# 3P4W_v1p2.net
KiCad netlist of a schematic drawn in EAGLE
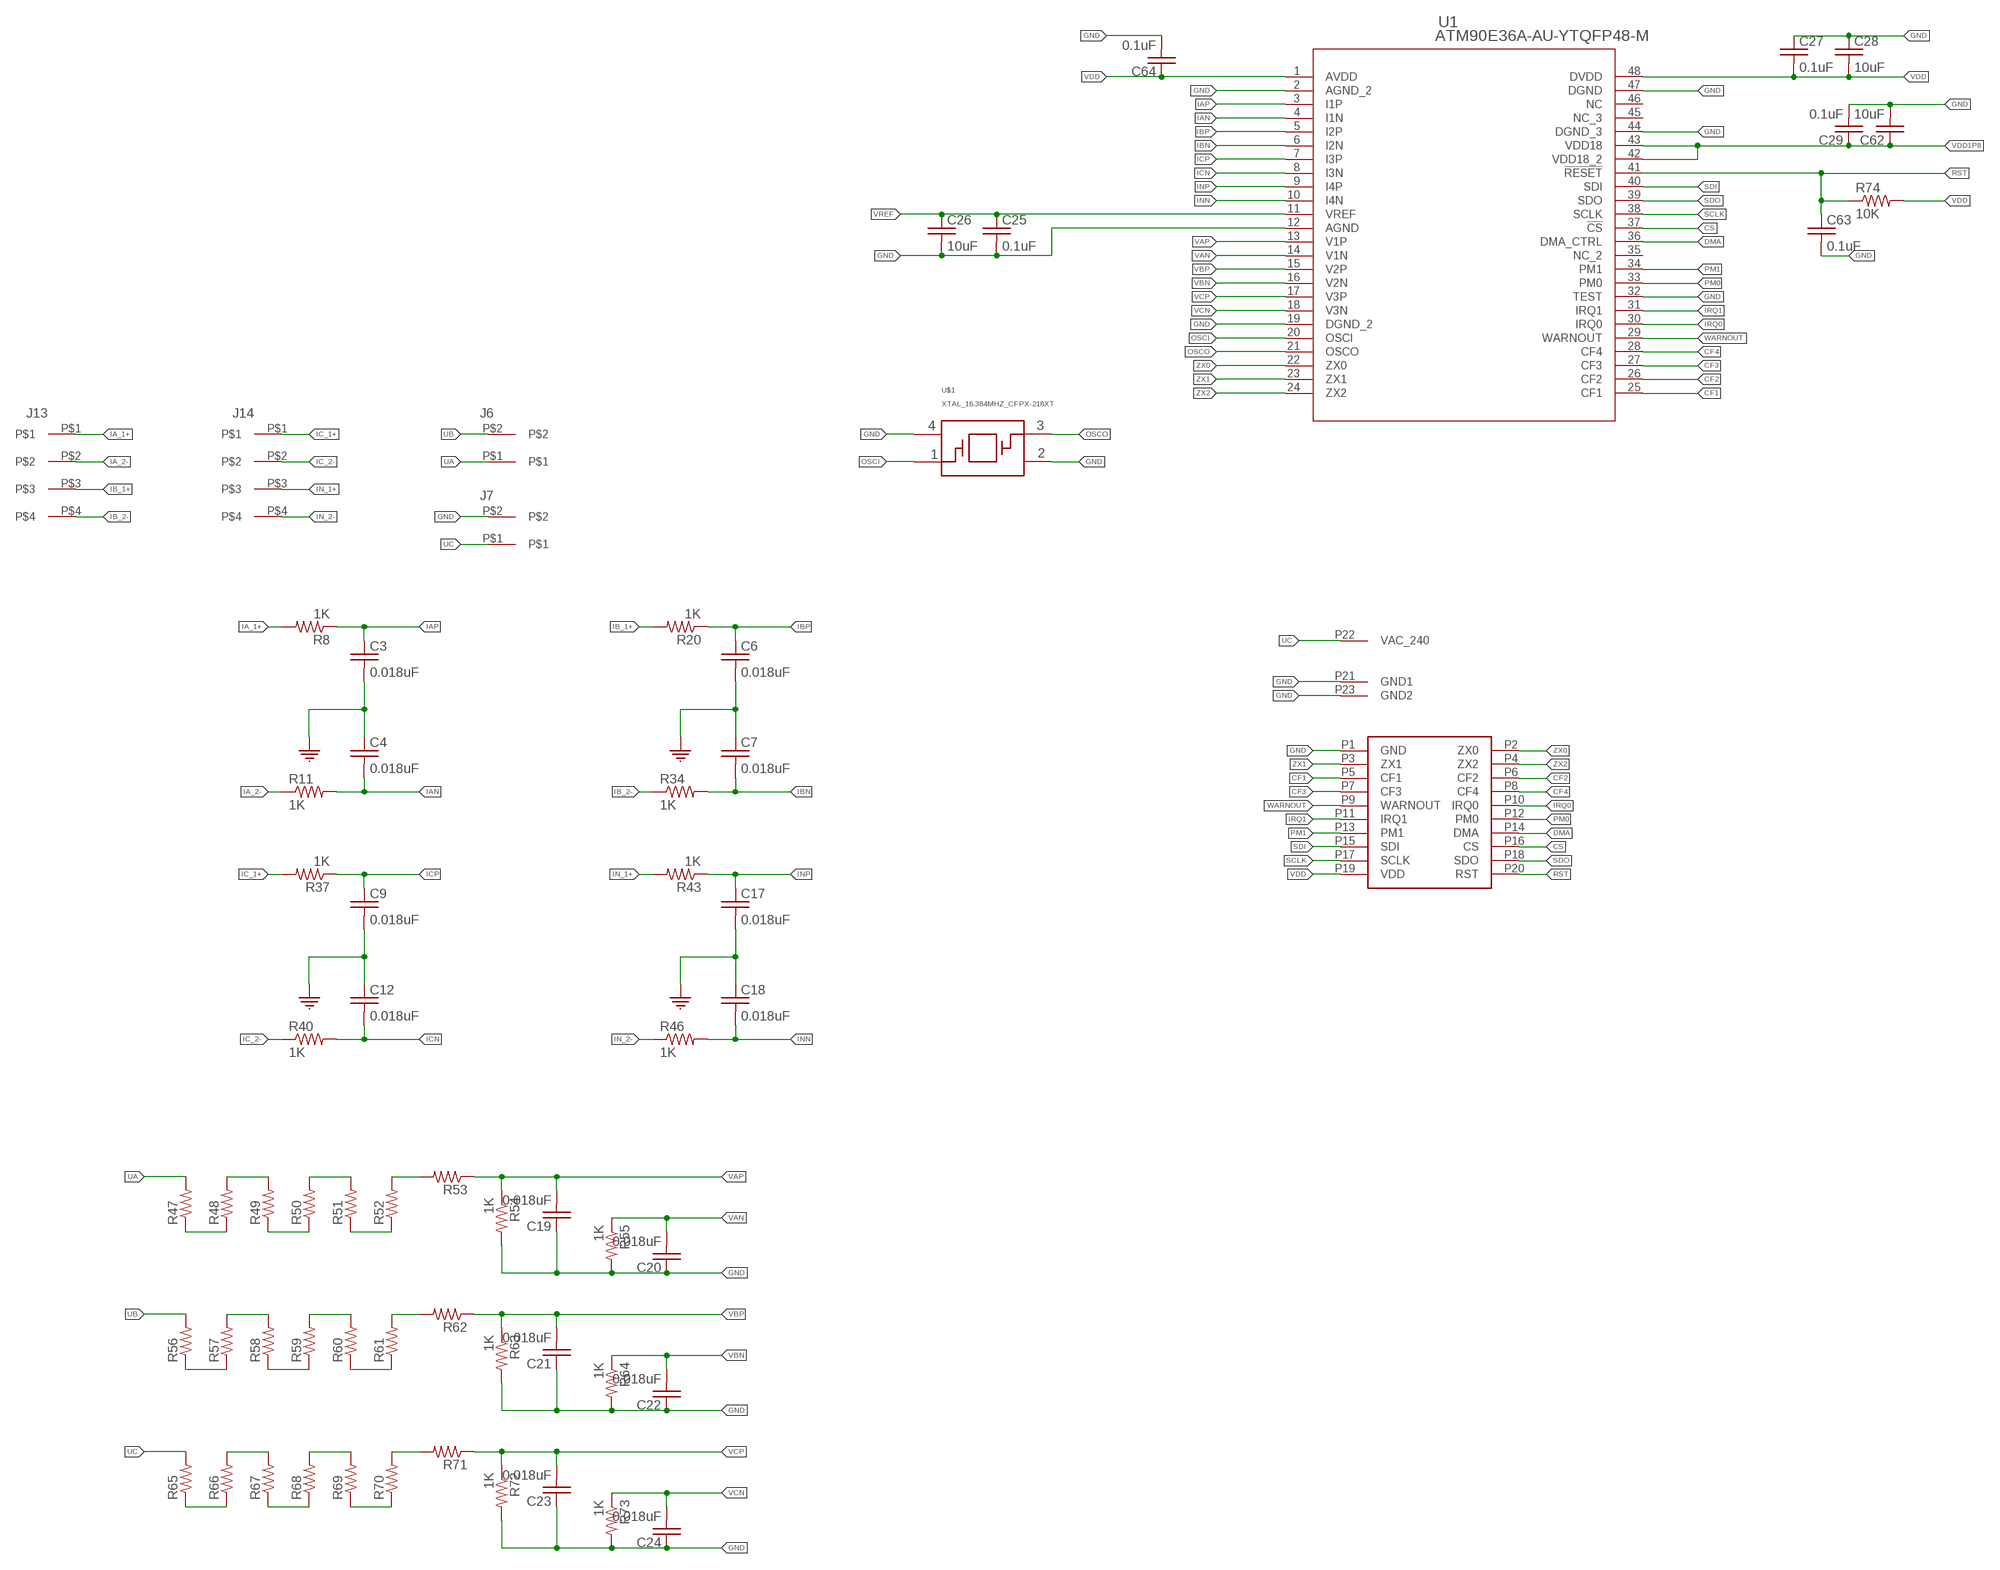
[diagram p0: schematic, sheet 1]

(export (version "E")
  (design (tool "Eeschema 10.0.6"))
  (components
    (comp (ref "C3")
      (value "0.018uF")
      (footprint "eagle-import:0402")
      (libsource (lib "eagle-import") (part "C_0402"))
    )
    (comp (ref "C4")
      (value "0.018uF")
      (footprint "eagle-import:0402")
      (libsource (lib "eagle-import") (part "C_0402"))
    )
    (comp (ref "C6")
      (value "0.018uF")
      (footprint "eagle-import:0402")
      (libsource (lib "eagle-import") (part "C_0402"))
    )
    (comp (ref "C7")
      (value "0.018uF")
      (footprint "eagle-import:0402")
      (libsource (lib "eagle-import") (part "C_0402"))
    )
    (comp (ref "C9")
      (value "0.018uF")
      (footprint "eagle-import:0402")
      (libsource (lib "eagle-import") (part "C_0402"))
    )
    (comp (ref "C12")
      (value "0.018uF")
      (footprint "eagle-import:0402")
      (libsource (lib "eagle-import") (part "C_0402"))
    )
    (comp (ref "C17")
      (value "0.018uF")
      (footprint "eagle-import:0402")
      (libsource (lib "eagle-import") (part "C_0402"))
    )
    (comp (ref "C18")
      (value "0.018uF")
      (footprint "eagle-import:0402")
      (libsource (lib "eagle-import") (part "C_0402"))
    )
    (comp (ref "C19")
      (value "0.018uF")
      (footprint "eagle-import:0402")
      (libsource (lib "eagle-import") (part "C_0402"))
    )
    (comp (ref "C20")
      (value "0.018uF")
      (footprint "eagle-import:0402")
      (libsource (lib "eagle-import") (part "C_0402"))
    )
    (comp (ref "C21")
      (value "0.018uF")
      (footprint "eagle-import:0402")
      (libsource (lib "eagle-import") (part "C_0402"))
    )
    (comp (ref "C22")
      (value "0.018uF")
      (footprint "eagle-import:0402")
      (libsource (lib "eagle-import") (part "C_0402"))
    )
    (comp (ref "C23")
      (value "0.018uF")
      (footprint "eagle-import:0402")
      (libsource (lib "eagle-import") (part "C_0402"))
    )
    (comp (ref "C24")
      (value "0.018uF")
      (footprint "eagle-import:0402")
      (libsource (lib "eagle-import") (part "C_0402"))
    )
    (comp (ref "C25")
      (value "0.1uF")
      (footprint "eagle-import:0402")
      (libsource (lib "eagle-import") (part "C_0402"))
    )
    (comp (ref "C26")
      (value "10uF")
      (footprint "eagle-import:0402")
      (libsource (lib "eagle-import") (part "C_0402"))
    )
    (comp (ref "C27")
      (value "0.1uF")
      (footprint "eagle-import:0402")
      (libsource (lib "eagle-import") (part "C_0402"))
    )
    (comp (ref "C28")
      (value "10uF")
      (footprint "eagle-import:0402")
      (libsource (lib "eagle-import") (part "C_0402"))
    )
    (comp (ref "C29")
      (value "0.1uF")
      (footprint "eagle-import:0402")
      (libsource (lib "eagle-import") (part "C_0402"))
    )
    (comp (ref "C62")
      (value "10uF")
      (footprint "eagle-import:0402")
      (libsource (lib "eagle-import") (part "C_0402"))
    )
    (comp (ref "C63")
      (value "0.1uF")
      (footprint "eagle-import:0402")
      (libsource (lib "eagle-import") (part "C_0402"))
    )
    (comp (ref "C64")
      (value "0.1uF")
      (footprint "eagle-import:0402")
      (libsource (lib "eagle-import") (part "C_0402"))
    )
    (comp (ref "J6")
      (value "3.81MM_1_X_2_RT_ANGLE_PLUG_HEADER")
      (footprint "eagle-import:2_3.81MM_PITCH")
      (libsource (lib "eagle-import") (part "3.81MM_1_X_2_RT_ANGLE_PLUG_HEADER"))
    )
    (comp (ref "J7")
      (value "3.81MM_1_X_2_RT_ANGLE_PLUG_HEADER")
      (footprint "eagle-import:2_3.81MM_PITCH")
      (libsource (lib "eagle-import") (part "3.81MM_1_X_2_RT_ANGLE_PLUG_HEADER"))
    )
    (comp (ref "J13")
      (value "3.81MM_1_X_4_RT_ANGLE_PLUG_HEADER")
      (footprint "eagle-import:1X4_3.81MM_PITCH")
      (libsource (lib "eagle-import") (part "3.81MM_1_X_4_RT_ANGLE_PLUG_HEADER"))
    )
    (comp (ref "J14")
      (value "3.81MM_1_X_4_RT_ANGLE_PLUG_HEADER")
      (footprint "eagle-import:1X4_3.81MM_PITCH")
      (libsource (lib "eagle-import") (part "3.81MM_1_X_4_RT_ANGLE_PLUG_HEADER"))
    )
    (comp (ref "R8")
      (value "1K")
      (footprint "eagle-import:0402")
      (libsource (lib "eagle-import") (part "R_0402"))
    )
    (comp (ref "R11")
      (value "1K")
      (footprint "eagle-import:0402")
      (libsource (lib "eagle-import") (part "R_0402"))
    )
    (comp (ref "R20")
      (value "1K")
      (footprint "eagle-import:0402")
      (libsource (lib "eagle-import") (part "R_0402"))
    )
    (comp (ref "R34")
      (value "1K")
      (footprint "eagle-import:0402")
      (libsource (lib "eagle-import") (part "R_0402"))
    )
    (comp (ref "R37")
      (value "1K")
      (footprint "eagle-import:0402")
      (libsource (lib "eagle-import") (part "R_0402"))
    )
    (comp (ref "R40")
      (value "1K")
      (footprint "eagle-import:0402")
      (libsource (lib "eagle-import") (part "R_0402"))
    )
    (comp (ref "R43")
      (value "1K")
      (footprint "eagle-import:0402")
      (libsource (lib "eagle-import") (part "R_0402"))
    )
    (comp (ref "R46")
      (value "1K")
      (footprint "eagle-import:0402")
      (libsource (lib "eagle-import") (part "R_0402"))
    )
    (comp (ref "R47")
      (value "R_0402")
      (footprint "eagle-import:0402")
      (libsource (lib "eagle-import") (part "R_0402"))
    )
    (comp (ref "R48")
      (value "R_0402")
      (footprint "eagle-import:0402")
      (libsource (lib "eagle-import") (part "R_0402"))
    )
    (comp (ref "R49")
      (value "R_0402")
      (footprint "eagle-import:0402")
      (libsource (lib "eagle-import") (part "R_0402"))
    )
    (comp (ref "R50")
      (value "R_0402")
      (footprint "eagle-import:0402")
      (libsource (lib "eagle-import") (part "R_0402"))
    )
    (comp (ref "R51")
      (value "R_0402")
      (footprint "eagle-import:0402")
      (libsource (lib "eagle-import") (part "R_0402"))
    )
    (comp (ref "R52")
      (value "R_0402")
      (footprint "eagle-import:0402")
      (libsource (lib "eagle-import") (part "R_0402"))
    )
    (comp (ref "R53")
      (value "R_0402")
      (footprint "eagle-import:0402")
      (libsource (lib "eagle-import") (part "R_0402"))
    )
    (comp (ref "R54")
      (value "1K")
      (footprint "eagle-import:0402")
      (libsource (lib "eagle-import") (part "R_0402"))
    )
    (comp (ref "R55")
      (value "1K")
      (footprint "eagle-import:0402")
      (libsource (lib "eagle-import") (part "R_0402"))
    )
    (comp (ref "R56")
      (value "R_0402")
      (footprint "eagle-import:0402")
      (libsource (lib "eagle-import") (part "R_0402"))
    )
    (comp (ref "R57")
      (value "R_0402")
      (footprint "eagle-import:0402")
      (libsource (lib "eagle-import") (part "R_0402"))
    )
    (comp (ref "R58")
      (value "R_0402")
      (footprint "eagle-import:0402")
      (libsource (lib "eagle-import") (part "R_0402"))
    )
    (comp (ref "R59")
      (value "R_0402")
      (footprint "eagle-import:0402")
      (libsource (lib "eagle-import") (part "R_0402"))
    )
    (comp (ref "R60")
      (value "R_0402")
      (footprint "eagle-import:0402")
      (libsource (lib "eagle-import") (part "R_0402"))
    )
    (comp (ref "R61")
      (value "R_0402")
      (footprint "eagle-import:0402")
      (libsource (lib "eagle-import") (part "R_0402"))
    )
    (comp (ref "R62")
      (value "R_0402")
      (footprint "eagle-import:0402")
      (libsource (lib "eagle-import") (part "R_0402"))
    )
    (comp (ref "R63")
      (value "1K")
      (footprint "eagle-import:0402")
      (libsource (lib "eagle-import") (part "R_0402"))
    )
    (comp (ref "R64")
      (value "1K")
      (footprint "eagle-import:0402")
      (libsource (lib "eagle-import") (part "R_0402"))
    )
    (comp (ref "R65")
      (value "R_0402")
      (footprint "eagle-import:0402")
      (libsource (lib "eagle-import") (part "R_0402"))
    )
    (comp (ref "R66")
      (value "R_0402")
      (footprint "eagle-import:0402")
      (libsource (lib "eagle-import") (part "R_0402"))
    )
    (comp (ref "R67")
      (value "R_0402")
      (footprint "eagle-import:0402")
      (libsource (lib "eagle-import") (part "R_0402"))
    )
    (comp (ref "R68")
      (value "R_0402")
      (footprint "eagle-import:0402")
      (libsource (lib "eagle-import") (part "R_0402"))
    )
    (comp (ref "R69")
      (value "R_0402")
      (footprint "eagle-import:0402")
      (libsource (lib "eagle-import") (part "R_0402"))
    )
    (comp (ref "R70")
      (value "R_0402")
      (footprint "eagle-import:0402")
      (libsource (lib "eagle-import") (part "R_0402"))
    )
    (comp (ref "R71")
      (value "R_0402")
      (footprint "eagle-import:0402")
      (libsource (lib "eagle-import") (part "R_0402"))
    )
    (comp (ref "R72")
      (value "1K")
      (footprint "eagle-import:0402")
      (libsource (lib "eagle-import") (part "R_0402"))
    )
    (comp (ref "R73")
      (value "1K")
      (footprint "eagle-import:0402")
      (libsource (lib "eagle-import") (part "R_0402"))
    )
    (comp (ref "R74")
      (value "10K")
      (footprint "eagle-import:0402")
      (libsource (lib "eagle-import") (part "R_0402"))
    )
    (comp (ref "U$1")
      (value "XTAL_16.384MHZ_CFPX-218XT")
      (footprint "eagle-import:XTAL_2.5X2.0")
      (libsource (lib "eagle-import") (part "XTAL_16.384MHZ_CFPX-218XT"))
    )
    (comp (ref "U$2")
      (value "METER_BASE")
      (footprint "eagle-import:METER_BASE")
      (libsource (lib "eagle-import") (part "METER_BASE"))
    )
    (comp (ref "U1")
      (value "ATM90E36A-AU-YTQFP48-M")
      (footprint "eagle-import:TQFP48-M")
      (fields (field (name "MANUFACTURER_PART_NUMBER") "ATM90E36AAUY"))
      (libsource (lib "eagle-import") (part "ATM90E36A-AU-YTQFP48-M"))
    )
  )
  (nets
    (net (code "1") (name "CF1") (class "Default")
      (node (ref "U$2") (pin "P5") (pinfunction "CF1_P5") (pintype "bidirectional"))
      (node (ref "U1") (pin "25") (pinfunction "CF1_25") (pintype "output"))
    )
    (net (code "2") (name "CF2") (class "Default")
      (node (ref "U$2") (pin "P6") (pinfunction "CF2_P6") (pintype "bidirectional"))
      (node (ref "U1") (pin "26") (pinfunction "CF2_26") (pintype "output"))
    )
    (net (code "3") (name "CF3") (class "Default")
      (node (ref "U$2") (pin "P7") (pinfunction "CF3_P7") (pintype "bidirectional"))
      (node (ref "U1") (pin "27") (pinfunction "CF3_27") (pintype "output"))
    )
    (net (code "4") (name "CF4") (class "Default")
      (node (ref "U$2") (pin "P8") (pinfunction "CF4_P8") (pintype "bidirectional"))
      (node (ref "U1") (pin "28") (pinfunction "CF4_28") (pintype "output"))
    )
    (net (code "5") (name "CS") (class "Default")
      (node (ref "U$2") (pin "P16") (pinfunction "CS_P16") (pintype "bidirectional"))
      (node (ref "U1") (pin "37") (pinfunction "~{CS}_37") (pintype "bidirectional"))
    )
    (net (code "6") (name "DMA") (class "Default")
      (node (ref "U$2") (pin "P14") (pinfunction "DMA_P14") (pintype "bidirectional"))
      (node (ref "U1") (pin "36") (pinfunction "DMA_CTRL_36") (pintype "input"))
    )
    (net (code "7") (name "GND") (class "Default")
      (node (ref "C12") (pin "P$1") (pinfunction "1_P$1") (pintype "passive"))
      (node (ref "C17") (pin "P$2") (pinfunction "2_P$2") (pintype "passive"))
      (node (ref "C18") (pin "P$1") (pinfunction "1_P$1") (pintype "passive"))
      (node (ref "C19") (pin "P$1") (pinfunction "1_P$1") (pintype "passive"))
      (node (ref "C20") (pin "P$1") (pinfunction "1_P$1") (pintype "passive"))
      (node (ref "C21") (pin "P$1") (pinfunction "1_P$1") (pintype "passive"))
      (node (ref "C22") (pin "P$1") (pinfunction "1_P$1") (pintype "passive"))
      (node (ref "C23") (pin "P$1") (pinfunction "1_P$1") (pintype "passive"))
      (node (ref "C24") (pin "P$1") (pinfunction "1_P$1") (pintype "passive"))
      (node (ref "C25") (pin "P$2") (pinfunction "2_P$2") (pintype "passive"))
      (node (ref "C26") (pin "P$2") (pinfunction "2_P$2") (pintype "passive"))
      (node (ref "C27") (pin "P$1") (pinfunction "1_P$1") (pintype "passive"))
      (node (ref "C28") (pin "P$1") (pinfunction "1_P$1") (pintype "passive"))
      (node (ref "C29") (pin "P$2") (pinfunction "2_P$2") (pintype "passive"))
      (node (ref "C3") (pin "P$2") (pinfunction "2_P$2") (pintype "passive"))
      (node (ref "C4") (pin "P$1") (pinfunction "1_P$1") (pintype "passive"))
      (node (ref "C6") (pin "P$2") (pinfunction "2_P$2") (pintype "passive"))
      (node (ref "C62") (pin "P$2") (pinfunction "2_P$2") (pintype "passive"))
      (node (ref "C63") (pin "P$2") (pinfunction "2_P$2") (pintype "passive"))
      (node (ref "C64") (pin "P$2") (pinfunction "2_P$2") (pintype "passive"))
      (node (ref "C7") (pin "P$1") (pinfunction "1_P$1") (pintype "passive"))
      (node (ref "C9") (pin "P$2") (pinfunction "2_P$2") (pintype "passive"))
      (node (ref "J7") (pin "P$2") (pinfunction "P$2_P$2") (pintype "bidirectional"))
      (node (ref "R54") (pin "P$2") (pinfunction "2_P$2") (pintype "passive"))
      (node (ref "R55") (pin "P$2") (pinfunction "2_P$2") (pintype "passive"))
      (node (ref "R63") (pin "P$2") (pinfunction "2_P$2") (pintype "passive"))
      (node (ref "R64") (pin "P$2") (pinfunction "2_P$2") (pintype "passive"))
      (node (ref "R72") (pin "P$2") (pinfunction "2_P$2") (pintype "passive"))
      (node (ref "R73") (pin "P$2") (pinfunction "2_P$2") (pintype "passive"))
      (node (ref "U$1") (pin "2") (pinfunction "2_2") (pintype "bidirectional"))
      (node (ref "U$1") (pin "4") (pinfunction "4_4") (pintype "bidirectional"))
      (node (ref "U$2") (pin "P1") (pinfunction "GND_P1") (pintype "bidirectional"))
      (node (ref "U$2") (pin "P21") (pinfunction "GND1_P21") (pintype "bidirectional"))
      (node (ref "U$2") (pin "P23") (pinfunction "GND2_P23") (pintype "bidirectional"))
      (node (ref "U1") (pin "12") (pinfunction "AGND_12") (pintype "power_in"))
      (node (ref "U1") (pin "19") (pinfunction "DGND_2_19") (pintype "power_in"))
      (node (ref "U1") (pin "2") (pinfunction "AGND_2_2") (pintype "power_in"))
      (node (ref "U1") (pin "32") (pinfunction "TEST_32") (pintype "input"))
      (node (ref "U1") (pin "44") (pinfunction "DGND_3_44") (pintype "power_in"))
      (node (ref "U1") (pin "47") (pinfunction "DGND_47") (pintype "power_in"))
    )
    (net (code "8") (name "IAN") (class "Default")
      (node (ref "C4") (pin "P$2") (pinfunction "2_P$2") (pintype "passive"))
      (node (ref "R11") (pin "P$2") (pinfunction "2_P$2") (pintype "passive"))
      (node (ref "U1") (pin "4") (pinfunction "I1N_4") (pintype "input"))
    )
    (net (code "9") (name "IAP") (class "Default")
      (node (ref "C3") (pin "P$1") (pinfunction "1_P$1") (pintype "passive"))
      (node (ref "R8") (pin "P$1") (pinfunction "1_P$1") (pintype "passive"))
      (node (ref "U1") (pin "3") (pinfunction "I1P_3") (pintype "input"))
    )
    (net (code "10") (name "IA_1+") (class "Default")
      (node (ref "J13") (pin "P$1") (pinfunction "P$1_P$1") (pintype "bidirectional"))
      (node (ref "R8") (pin "P$2") (pinfunction "2_P$2") (pintype "passive"))
    )
    (net (code "11") (name "IA_2-") (class "Default")
      (node (ref "J13") (pin "P$2") (pinfunction "P$2_P$2") (pintype "bidirectional"))
      (node (ref "R11") (pin "P$1") (pinfunction "1_P$1") (pintype "passive"))
    )
    (net (code "12") (name "IBN") (class "Default")
      (node (ref "C7") (pin "P$2") (pinfunction "2_P$2") (pintype "passive"))
      (node (ref "R34") (pin "P$2") (pinfunction "2_P$2") (pintype "passive"))
      (node (ref "U1") (pin "6") (pinfunction "I2N_6") (pintype "input"))
    )
    (net (code "13") (name "IBP") (class "Default")
      (node (ref "C6") (pin "P$1") (pinfunction "1_P$1") (pintype "passive"))
      (node (ref "R20") (pin "P$1") (pinfunction "1_P$1") (pintype "passive"))
      (node (ref "U1") (pin "5") (pinfunction "I2P_5") (pintype "input"))
    )
    (net (code "14") (name "IB_1+") (class "Default")
      (node (ref "J13") (pin "P$3") (pinfunction "P$3_P$3") (pintype "bidirectional"))
      (node (ref "R20") (pin "P$2") (pinfunction "2_P$2") (pintype "passive"))
    )
    (net (code "15") (name "IB_2-") (class "Default")
      (node (ref "J13") (pin "P$4") (pinfunction "P$4_P$4") (pintype "bidirectional"))
      (node (ref "R34") (pin "P$1") (pinfunction "1_P$1") (pintype "passive"))
    )
    (net (code "16") (name "ICN") (class "Default")
      (node (ref "C12") (pin "P$2") (pinfunction "2_P$2") (pintype "passive"))
      (node (ref "R40") (pin "P$2") (pinfunction "2_P$2") (pintype "passive"))
      (node (ref "U1") (pin "8") (pinfunction "I3N_8") (pintype "input"))
    )
    (net (code "17") (name "ICP") (class "Default")
      (node (ref "C9") (pin "P$1") (pinfunction "1_P$1") (pintype "passive"))
      (node (ref "R37") (pin "P$1") (pinfunction "1_P$1") (pintype "passive"))
      (node (ref "U1") (pin "7") (pinfunction "I3P_7") (pintype "input"))
    )
    (net (code "18") (name "IC_1+") (class "Default")
      (node (ref "J14") (pin "P$1") (pinfunction "P$1_P$1") (pintype "bidirectional"))
      (node (ref "R37") (pin "P$2") (pinfunction "2_P$2") (pintype "passive"))
    )
    (net (code "19") (name "IC_2-") (class "Default")
      (node (ref "J14") (pin "P$2") (pinfunction "P$2_P$2") (pintype "bidirectional"))
      (node (ref "R40") (pin "P$1") (pinfunction "1_P$1") (pintype "passive"))
    )
    (net (code "20") (name "INN") (class "Default")
      (node (ref "C18") (pin "P$2") (pinfunction "2_P$2") (pintype "passive"))
      (node (ref "R46") (pin "P$2") (pinfunction "2_P$2") (pintype "passive"))
      (node (ref "U1") (pin "10") (pinfunction "I4N_10") (pintype "input"))
    )
    (net (code "21") (name "INP") (class "Default")
      (node (ref "C17") (pin "P$1") (pinfunction "1_P$1") (pintype "passive"))
      (node (ref "R43") (pin "P$1") (pinfunction "1_P$1") (pintype "passive"))
      (node (ref "U1") (pin "9") (pinfunction "I4P_9") (pintype "input"))
    )
    (net (code "22") (name "IN_1+") (class "Default")
      (node (ref "J14") (pin "P$3") (pinfunction "P$3_P$3") (pintype "bidirectional"))
      (node (ref "R43") (pin "P$2") (pinfunction "2_P$2") (pintype "passive"))
    )
    (net (code "23") (name "IN_2-") (class "Default")
      (node (ref "J14") (pin "P$4") (pinfunction "P$4_P$4") (pintype "bidirectional"))
      (node (ref "R46") (pin "P$1") (pinfunction "1_P$1") (pintype "passive"))
    )
    (net (code "24") (name "IRQ0") (class "Default")
      (node (ref "U$2") (pin "P10") (pinfunction "IRQ0_P10") (pintype "bidirectional"))
      (node (ref "U1") (pin "30") (pinfunction "IRQ0_30") (pintype "output"))
    )
    (net (code "25") (name "IRQ1") (class "Default")
      (node (ref "U$2") (pin "P11") (pinfunction "IRQ1_P11") (pintype "bidirectional"))
      (node (ref "U1") (pin "31") (pinfunction "IRQ1_31") (pintype "output"))
    )
    (net (code "26") (name "Net-(R47-1)") (class "Default")
      (node (ref "R47") (pin "P$1") (pinfunction "1_P$1") (pintype "passive"))
      (node (ref "R48") (pin "P$1") (pinfunction "1_P$1") (pintype "passive"))
    )
    (net (code "27") (name "Net-(R48-2)") (class "Default")
      (node (ref "R48") (pin "P$2") (pinfunction "2_P$2") (pintype "passive"))
      (node (ref "R49") (pin "P$2") (pinfunction "2_P$2") (pintype "passive"))
    )
    (net (code "28") (name "Net-(R49-1)") (class "Default")
      (node (ref "R49") (pin "P$1") (pinfunction "1_P$1") (pintype "passive"))
      (node (ref "R50") (pin "P$1") (pinfunction "1_P$1") (pintype "passive"))
    )
    (net (code "29") (name "Net-(R50-2)") (class "Default")
      (node (ref "R50") (pin "P$2") (pinfunction "2_P$2") (pintype "passive"))
      (node (ref "R51") (pin "P$2") (pinfunction "2_P$2") (pintype "passive"))
    )
    (net (code "30") (name "Net-(R51-1)") (class "Default")
      (node (ref "R51") (pin "P$1") (pinfunction "1_P$1") (pintype "passive"))
      (node (ref "R52") (pin "P$1") (pinfunction "1_P$1") (pintype "passive"))
    )
    (net (code "31") (name "Net-(R52-2)") (class "Default")
      (node (ref "R52") (pin "P$2") (pinfunction "2_P$2") (pintype "passive"))
      (node (ref "R53") (pin "P$2") (pinfunction "2_P$2") (pintype "passive"))
    )
    (net (code "32") (name "Net-(R56-1)") (class "Default")
      (node (ref "R56") (pin "P$1") (pinfunction "1_P$1") (pintype "passive"))
      (node (ref "R57") (pin "P$1") (pinfunction "1_P$1") (pintype "passive"))
    )
    (net (code "33") (name "Net-(R57-2)") (class "Default")
      (node (ref "R57") (pin "P$2") (pinfunction "2_P$2") (pintype "passive"))
      (node (ref "R58") (pin "P$2") (pinfunction "2_P$2") (pintype "passive"))
    )
    (net (code "34") (name "Net-(R58-1)") (class "Default")
      (node (ref "R58") (pin "P$1") (pinfunction "1_P$1") (pintype "passive"))
      (node (ref "R59") (pin "P$1") (pinfunction "1_P$1") (pintype "passive"))
    )
    (net (code "35") (name "Net-(R59-2)") (class "Default")
      (node (ref "R59") (pin "P$2") (pinfunction "2_P$2") (pintype "passive"))
      (node (ref "R60") (pin "P$2") (pinfunction "2_P$2") (pintype "passive"))
    )
    (net (code "36") (name "Net-(R60-1)") (class "Default")
      (node (ref "R60") (pin "P$1") (pinfunction "1_P$1") (pintype "passive"))
      (node (ref "R61") (pin "P$1") (pinfunction "1_P$1") (pintype "passive"))
    )
    (net (code "37") (name "Net-(R61-2)") (class "Default")
      (node (ref "R61") (pin "P$2") (pinfunction "2_P$2") (pintype "passive"))
      (node (ref "R62") (pin "P$2") (pinfunction "2_P$2") (pintype "passive"))
    )
    (net (code "38") (name "Net-(R65-1)") (class "Default")
      (node (ref "R65") (pin "P$1") (pinfunction "1_P$1") (pintype "passive"))
      (node (ref "R66") (pin "P$1") (pinfunction "1_P$1") (pintype "passive"))
    )
    (net (code "39") (name "Net-(R66-2)") (class "Default")
      (node (ref "R66") (pin "P$2") (pinfunction "2_P$2") (pintype "passive"))
      (node (ref "R67") (pin "P$2") (pinfunction "2_P$2") (pintype "passive"))
    )
    (net (code "40") (name "Net-(R67-1)") (class "Default")
      (node (ref "R67") (pin "P$1") (pinfunction "1_P$1") (pintype "passive"))
      (node (ref "R68") (pin "P$1") (pinfunction "1_P$1") (pintype "passive"))
    )
    (net (code "41") (name "Net-(R68-2)") (class "Default")
      (node (ref "R68") (pin "P$2") (pinfunction "2_P$2") (pintype "passive"))
      (node (ref "R69") (pin "P$2") (pinfunction "2_P$2") (pintype "passive"))
    )
    (net (code "42") (name "Net-(R69-1)") (class "Default")
      (node (ref "R69") (pin "P$1") (pinfunction "1_P$1") (pintype "passive"))
      (node (ref "R70") (pin "P$1") (pinfunction "1_P$1") (pintype "passive"))
    )
    (net (code "43") (name "Net-(R70-2)") (class "Default")
      (node (ref "R70") (pin "P$2") (pinfunction "2_P$2") (pintype "passive"))
      (node (ref "R71") (pin "P$2") (pinfunction "2_P$2") (pintype "passive"))
    )
    (net (code "44") (name "OSCI") (class "Default")
      (node (ref "U$1") (pin "1") (pinfunction "1_1") (pintype "bidirectional"))
      (node (ref "U1") (pin "20") (pinfunction "OSCI_20") (pintype "input"))
    )
    (net (code "45") (name "OSCO") (class "Default")
      (node (ref "U$1") (pin "3") (pinfunction "3_3") (pintype "bidirectional"))
      (node (ref "U1") (pin "21") (pinfunction "OSCO_21") (pintype "output"))
    )
    (net (code "46") (name "PM0") (class "Default")
      (node (ref "U$2") (pin "P12") (pinfunction "PM0_P12") (pintype "bidirectional"))
      (node (ref "U1") (pin "33") (pinfunction "PM0_33") (pintype "input"))
    )
    (net (code "47") (name "PM1") (class "Default")
      (node (ref "U$2") (pin "P13") (pinfunction "PM1_P13") (pintype "bidirectional"))
      (node (ref "U1") (pin "34") (pinfunction "PM1_34") (pintype "input"))
    )
    (net (code "48") (name "RST") (class "Default")
      (node (ref "C63") (pin "P$1") (pinfunction "1_P$1") (pintype "passive"))
      (node (ref "R74") (pin "P$1") (pinfunction "1_P$1") (pintype "passive"))
      (node (ref "U$2") (pin "P20") (pinfunction "RST_P20") (pintype "bidirectional"))
      (node (ref "U1") (pin "41") (pinfunction "~{RESET}_41") (pintype "input"))
    )
    (net (code "49") (name "SCLK") (class "Default")
      (node (ref "U$2") (pin "P17") (pinfunction "SCLK_P17") (pintype "bidirectional"))
      (node (ref "U1") (pin "38") (pinfunction "SCLK_38") (pintype "bidirectional"))
    )
    (net (code "50") (name "SDI") (class "Default")
      (node (ref "U$2") (pin "P15") (pinfunction "SDI_P15") (pintype "bidirectional"))
      (node (ref "U1") (pin "40") (pinfunction "SDI_40") (pintype "bidirectional"))
    )
    (net (code "51") (name "SDO") (class "Default")
      (node (ref "U$2") (pin "P18") (pinfunction "SDO_P18") (pintype "bidirectional"))
      (node (ref "U1") (pin "39") (pinfunction "SDO_39") (pintype "bidirectional"))
    )
    (net (code "52") (name "UA") (class "Default")
      (node (ref "J6") (pin "P$1") (pinfunction "P$1_P$1") (pintype "bidirectional"))
      (node (ref "R47") (pin "P$2") (pinfunction "2_P$2") (pintype "passive"))
    )
    (net (code "53") (name "UB") (class "Default")
      (node (ref "J6") (pin "P$2") (pinfunction "P$2_P$2") (pintype "bidirectional"))
      (node (ref "R56") (pin "P$2") (pinfunction "2_P$2") (pintype "passive"))
    )
    (net (code "54") (name "UC") (class "Default")
      (node (ref "J7") (pin "P$1") (pinfunction "P$1_P$1") (pintype "bidirectional"))
      (node (ref "R65") (pin "P$2") (pinfunction "2_P$2") (pintype "passive"))
      (node (ref "U$2") (pin "P22") (pinfunction "VAC_240_P22") (pintype "bidirectional"))
    )
    (net (code "55") (name "VAN") (class "Default")
      (node (ref "C20") (pin "P$2") (pinfunction "2_P$2") (pintype "passive"))
      (node (ref "R55") (pin "P$1") (pinfunction "1_P$1") (pintype "passive"))
      (node (ref "U1") (pin "14") (pinfunction "V1N_14") (pintype "input"))
    )
    (net (code "56") (name "VAP") (class "Default")
      (node (ref "C19") (pin "P$2") (pinfunction "2_P$2") (pintype "passive"))
      (node (ref "R53") (pin "P$1") (pinfunction "1_P$1") (pintype "passive"))
      (node (ref "R54") (pin "P$1") (pinfunction "1_P$1") (pintype "passive"))
      (node (ref "U1") (pin "13") (pinfunction "V1P_13") (pintype "input"))
    )
    (net (code "57") (name "VBN") (class "Default")
      (node (ref "C22") (pin "P$2") (pinfunction "2_P$2") (pintype "passive"))
      (node (ref "R64") (pin "P$1") (pinfunction "1_P$1") (pintype "passive"))
      (node (ref "U1") (pin "16") (pinfunction "V2N_16") (pintype "input"))
    )
    (net (code "58") (name "VBP") (class "Default")
      (node (ref "C21") (pin "P$2") (pinfunction "2_P$2") (pintype "passive"))
      (node (ref "R62") (pin "P$1") (pinfunction "1_P$1") (pintype "passive"))
      (node (ref "R63") (pin "P$1") (pinfunction "1_P$1") (pintype "passive"))
      (node (ref "U1") (pin "15") (pinfunction "V2P_15") (pintype "input"))
    )
    (net (code "59") (name "VCN") (class "Default")
      (node (ref "C24") (pin "P$2") (pinfunction "2_P$2") (pintype "passive"))
      (node (ref "R73") (pin "P$1") (pinfunction "1_P$1") (pintype "passive"))
      (node (ref "U1") (pin "18") (pinfunction "V3N_18") (pintype "input"))
    )
    (net (code "60") (name "VCP") (class "Default")
      (node (ref "C23") (pin "P$2") (pinfunction "2_P$2") (pintype "passive"))
      (node (ref "R71") (pin "P$1") (pinfunction "1_P$1") (pintype "passive"))
      (node (ref "R72") (pin "P$1") (pinfunction "1_P$1") (pintype "passive"))
      (node (ref "U1") (pin "17") (pinfunction "V3P_17") (pintype "input"))
    )
    (net (code "61") (name "VDD") (class "Default")
      (node (ref "C27") (pin "P$2") (pinfunction "2_P$2") (pintype "passive"))
      (node (ref "C28") (pin "P$2") (pinfunction "2_P$2") (pintype "passive"))
      (node (ref "C64") (pin "P$1") (pinfunction "1_P$1") (pintype "passive"))
      (node (ref "R74") (pin "P$2") (pinfunction "2_P$2") (pintype "passive"))
      (node (ref "U$2") (pin "P19") (pinfunction "VDD_P19") (pintype "bidirectional"))
      (node (ref "U1") (pin "1") (pinfunction "AVDD_1") (pintype "power_in"))
      (node (ref "U1") (pin "48") (pinfunction "DVDD_48") (pintype "power_in"))
    )
    (net (code "62") (name "VDD1P8") (class "Default")
      (node (ref "C29") (pin "P$1") (pinfunction "1_P$1") (pintype "passive"))
      (node (ref "C62") (pin "P$1") (pinfunction "1_P$1") (pintype "passive"))
      (node (ref "U1") (pin "42") (pinfunction "VDD18_2_42") (pintype "power_in"))
      (node (ref "U1") (pin "43") (pinfunction "VDD18_43") (pintype "power_in"))
    )
    (net (code "63") (name "VREF") (class "Default")
      (node (ref "C25") (pin "P$1") (pinfunction "1_P$1") (pintype "passive"))
      (node (ref "C26") (pin "P$1") (pinfunction "1_P$1") (pintype "passive"))
      (node (ref "U1") (pin "11") (pinfunction "VREF_11") (pintype "output"))
    )
    (net (code "64") (name "WARNOUT") (class "Default")
      (node (ref "U$2") (pin "P9") (pinfunction "WARNOUT_P9") (pintype "bidirectional"))
      (node (ref "U1") (pin "29") (pinfunction "WARNOUT_29") (pintype "output"))
    )
    (net (code "65") (name "ZX0") (class "Default")
      (node (ref "U$2") (pin "P2") (pinfunction "ZX0_P2") (pintype "bidirectional"))
      (node (ref "U1") (pin "22") (pinfunction "ZX0_22") (pintype "output"))
    )
    (net (code "66") (name "ZX1") (class "Default")
      (node (ref "U$2") (pin "P3") (pinfunction "ZX1_P3") (pintype "bidirectional"))
      (node (ref "U1") (pin "23") (pinfunction "ZX1_23") (pintype "output"))
    )
    (net (code "67") (name "ZX2") (class "Default")
      (node (ref "U$2") (pin "P4") (pinfunction "ZX2_P4") (pintype "bidirectional"))
      (node (ref "U1") (pin "24") (pinfunction "ZX2_24") (pintype "output"))
    )
    (net (code "68") (name "unconnected-(U1-NC-Pad46)") (class "Default")
      (node (ref "U1") (pin "46") (pinfunction "NC_46") (pintype "no_connect"))
    )
    (net (code "69") (name "unconnected-(U1-NC_2-Pad35)") (class "Default")
      (node (ref "U1") (pin "35") (pinfunction "NC_2_35") (pintype "no_connect"))
    )
    (net (code "70") (name "unconnected-(U1-NC_3-Pad45)") (class "Default")
      (node (ref "U1") (pin "45") (pinfunction "NC_3_45") (pintype "no_connect"))
    )
  )
)
